# Drivers_Matrices.net
KiCad netlist of a schematic drawn in Altium Designer
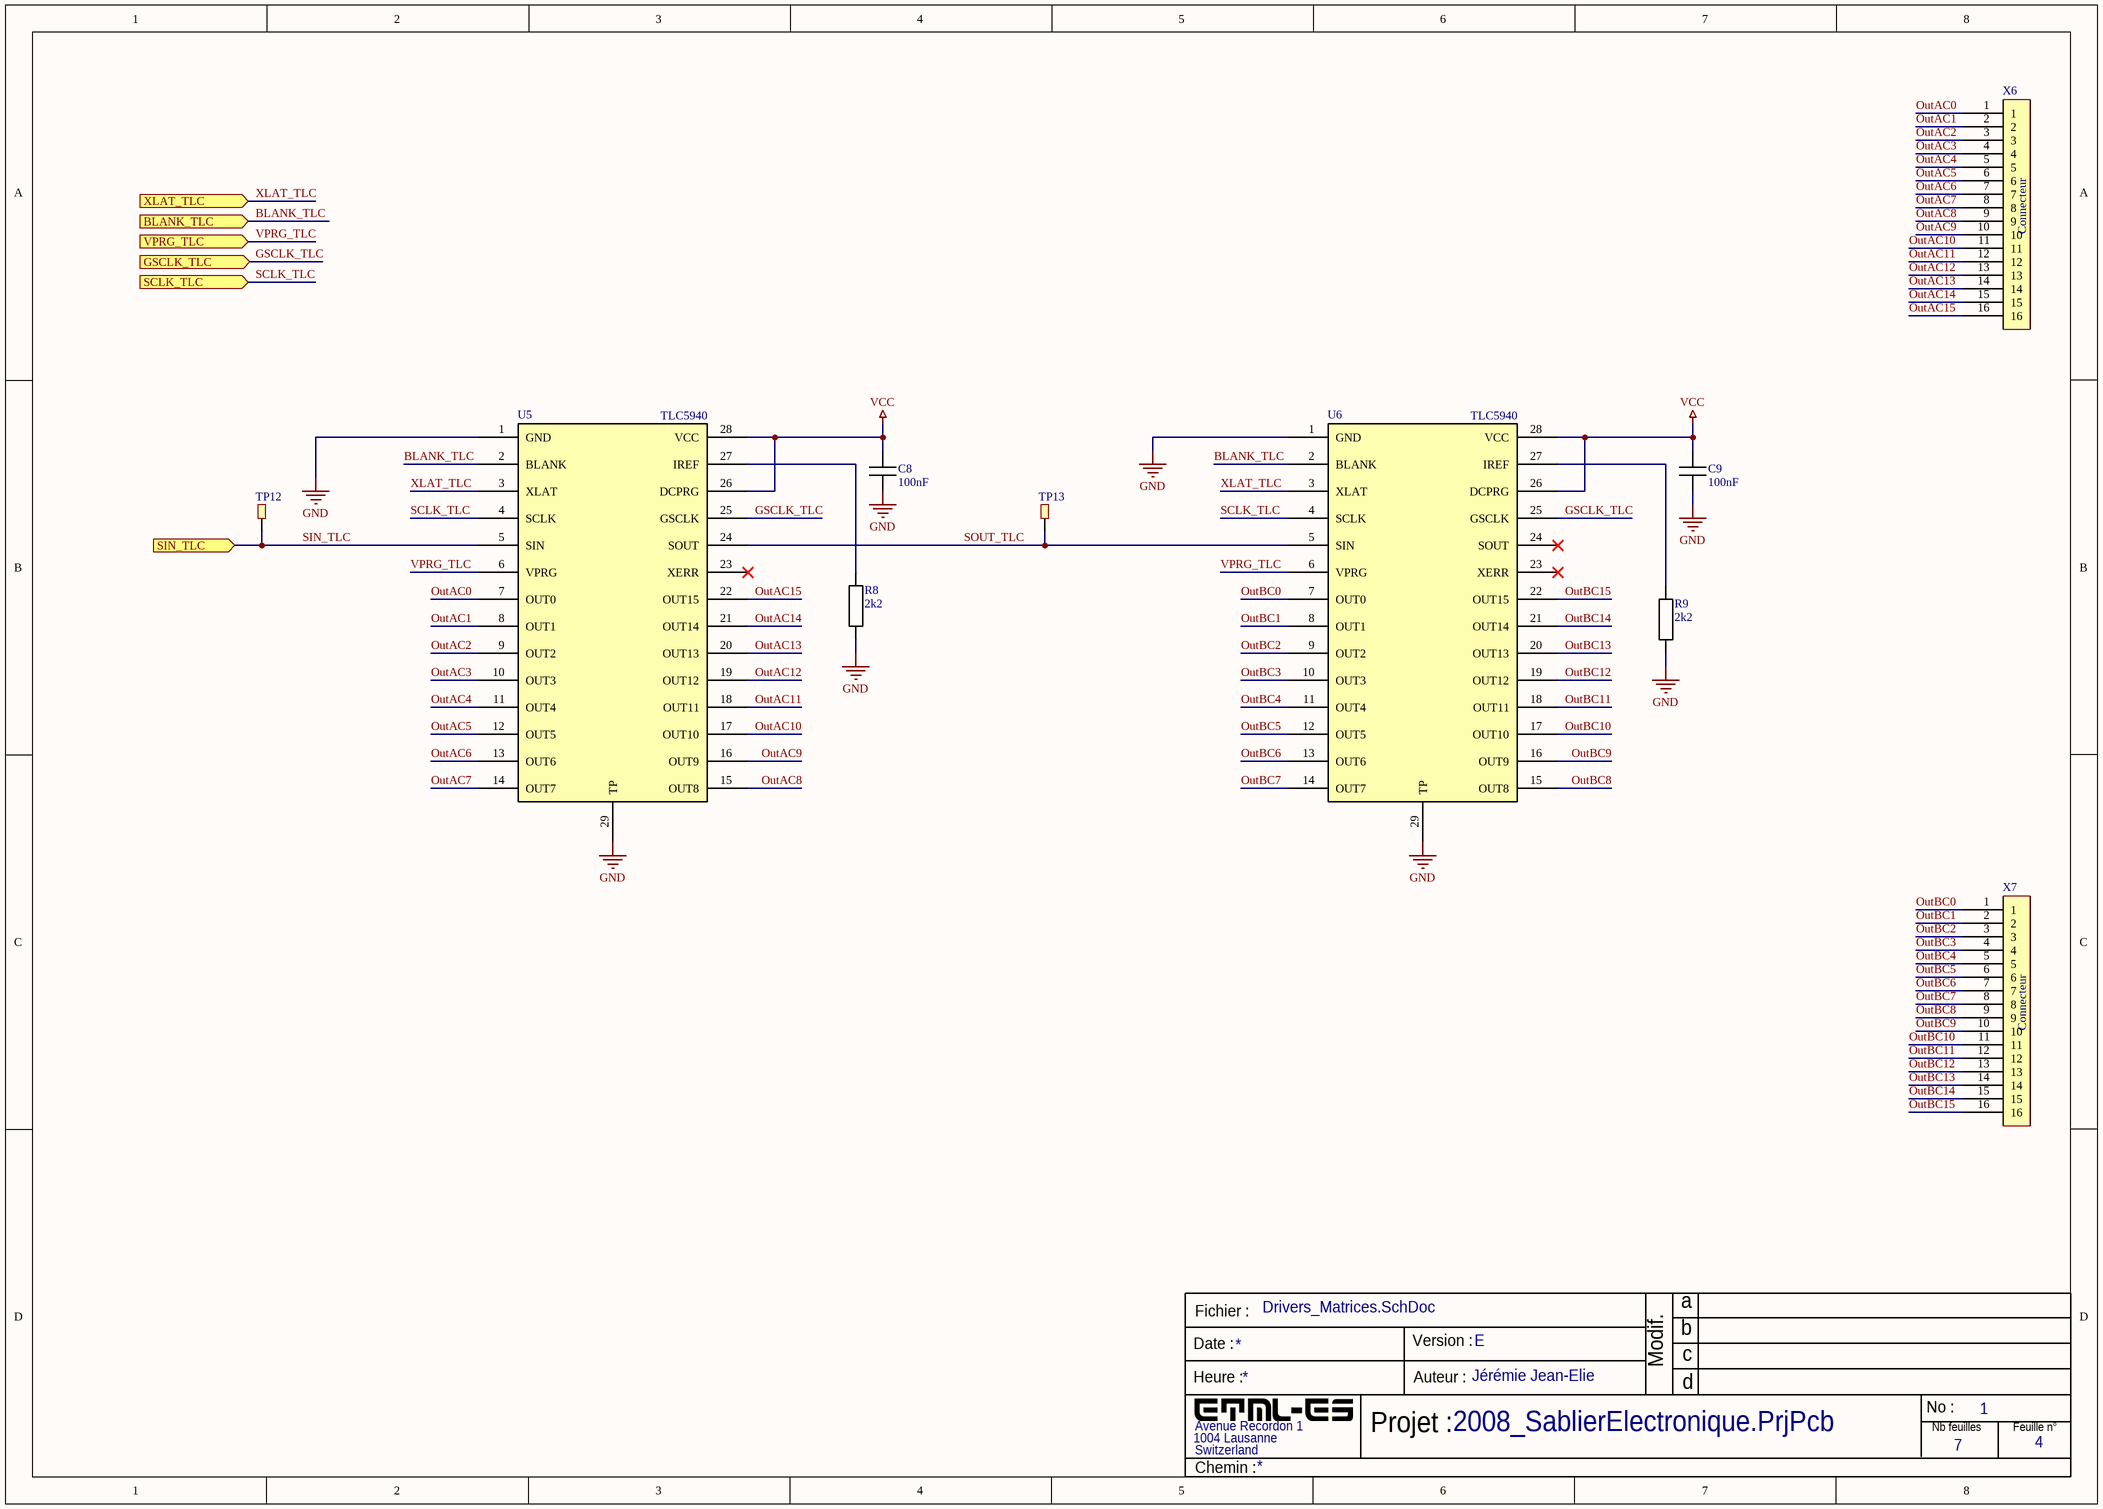
[diagram p0: Drivers_Matrices.SchDoc]

(export (version "E")
  (design (tool "Eeschema 10.0.6"))
  (components
    (comp (ref "C8")
      (value "100nF")
      (footprint "CAPC1608X08M")
      (description "CAPC 100nF X7R 50V 10% 1608 (0603 INCH)")
      (fields (field (name "VOLTAGE") "50V") (field (name "MANUFACTURER") "TDK"))
      (libsource (lib "ETML-ES") (part "CAP"))
    )
    (comp (ref "C9")
      (value "100nF")
      (footprint "CAPC1608X08M")
      (description "CAPC 100nF X7R 50V 10% 1608 (0603 INCH)")
      (fields (field (name "VOLTAGE") "50V") (field (name "MANUFACTURER") "TDK"))
      (libsource (lib "ETML-ES") (part "CAP"))
    )
    (comp (ref "R8")
      (value "2k2")
      (footprint "RESC1608X06M")
      (description "RES 2.2kohm  ±1% 0.1W  1608 (0603 INCH)")
      (fields (field (name "POWER") "0.1W") (field (name "VOLTAGE") "75V"))
      (libsource (lib "ETML-ES") (part "RES"))
    )
    (comp (ref "R9")
      (value "2k2")
      (footprint "RESC1608X06M")
      (description "RES 2.2kohm  ±1% 0.1W  1608 (0603 INCH)")
      (fields (field (name "POWER") "0.1W") (field (name "VOLTAGE") "75V"))
      (libsource (lib "ETML-ES") (part "RES"))
    )
    (comp (ref "TP12")
      (value "TestPoint")
      (footprint "KEYSTONE_5019")
      (libsource (lib "Schlib1") (part "TestPoint"))
    )
    (comp (ref "TP13")
      (value "TestPoint")
      (footprint "KEYSTONE_5019")
      (libsource (lib "Schlib1") (part "TestPoint"))
    )
    (comp (ref "U5")
      (value "TLC5940")
      (footprint "TSOP65P640X120_HS-29N")
      (libsource (lib "Schlib1") (part "TLC5940"))
    )
    (comp (ref "U6")
      (value "TLC5940")
      (footprint "TSOP65P640X120_HS-29N")
      (libsource (lib "Schlib1") (part "TLC5940"))
    )
    (comp (ref "X6")
      (value "~")
      (footprint "MOLEX_2x8")
      (libsource (lib "2008_SablierElectronique_SCHLIB") (part "Mâle DIN 8 x 8"))
    )
    (comp (ref "X7")
      (value "~")
      (footprint "MOLEX_2x8")
      (libsource (lib "2008_SablierElectronique_SCHLIB") (part "Mâle DIN 8 x 8"))
    )
  )
  (nets
    (net (code "1") (name "/BLANK_TLC") (class "Default")
      (node (ref "U5") (pin "2") (pinfunction "BLANK_2") (pintype "passive"))
      (node (ref "U6") (pin "2") (pinfunction "BLANK_2") (pintype "passive"))
    )
    (net (code "2") (name "/GSCLK_TLC") (class "Default")
      (node (ref "U5") (pin "25") (pinfunction "GSCLK_25") (pintype "passive"))
      (node (ref "U6") (pin "25") (pinfunction "GSCLK_25") (pintype "passive"))
    )
    (net (code "3") (name "/OutAC0") (class "Default")
      (node (ref "U5") (pin "7") (pinfunction "OUT0_7") (pintype "passive"))
      (node (ref "X6") (pin "1") (pinfunction "1_1") (pintype "passive"))
    )
    (net (code "4") (name "/OutAC1") (class "Default")
      (node (ref "U5") (pin "8") (pinfunction "OUT1_8") (pintype "passive"))
      (node (ref "X6") (pin "2") (pinfunction "2_2") (pintype "passive"))
    )
    (net (code "5") (name "/OutAC2") (class "Default")
      (node (ref "U5") (pin "9") (pinfunction "OUT2_9") (pintype "passive"))
      (node (ref "X6") (pin "3") (pinfunction "3_3") (pintype "passive"))
    )
    (net (code "6") (name "/OutAC3") (class "Default")
      (node (ref "U5") (pin "10") (pinfunction "OUT3_10") (pintype "passive"))
      (node (ref "X6") (pin "4") (pinfunction "4_4") (pintype "passive"))
    )
    (net (code "7") (name "/OutAC4") (class "Default")
      (node (ref "U5") (pin "11") (pinfunction "OUT4_11") (pintype "passive"))
      (node (ref "X6") (pin "5") (pinfunction "5_5") (pintype "passive"))
    )
    (net (code "8") (name "/OutAC5") (class "Default")
      (node (ref "U5") (pin "12") (pinfunction "OUT5_12") (pintype "passive"))
      (node (ref "X6") (pin "6") (pinfunction "6_6") (pintype "passive"))
    )
    (net (code "9") (name "/OutAC6") (class "Default")
      (node (ref "U5") (pin "13") (pinfunction "OUT6_13") (pintype "passive"))
      (node (ref "X6") (pin "7") (pinfunction "7_7") (pintype "passive"))
    )
    (net (code "10") (name "/OutAC7") (class "Default")
      (node (ref "U5") (pin "14") (pinfunction "OUT7_14") (pintype "passive"))
      (node (ref "X6") (pin "8") (pinfunction "8_8") (pintype "passive"))
    )
    (net (code "11") (name "/OutAC8") (class "Default")
      (node (ref "U5") (pin "15") (pinfunction "OUT8_15") (pintype "passive"))
      (node (ref "X6") (pin "9") (pinfunction "9_9") (pintype "passive"))
    )
    (net (code "12") (name "/OutAC9") (class "Default")
      (node (ref "U5") (pin "16") (pinfunction "OUT9_16") (pintype "passive"))
      (node (ref "X6") (pin "10") (pinfunction "10_10") (pintype "passive"))
    )
    (net (code "13") (name "/OutAC10") (class "Default")
      (node (ref "U5") (pin "17") (pinfunction "OUT10_17") (pintype "passive"))
      (node (ref "X6") (pin "11") (pinfunction "11_11") (pintype "passive"))
    )
    (net (code "14") (name "/OutAC11") (class "Default")
      (node (ref "U5") (pin "18") (pinfunction "OUT11_18") (pintype "passive"))
      (node (ref "X6") (pin "12") (pinfunction "12_12") (pintype "passive"))
    )
    (net (code "15") (name "/OutAC12") (class "Default")
      (node (ref "U5") (pin "19") (pinfunction "OUT12_19") (pintype "passive"))
      (node (ref "X6") (pin "13") (pinfunction "13_13") (pintype "passive"))
    )
    (net (code "16") (name "/OutAC13") (class "Default")
      (node (ref "U5") (pin "20") (pinfunction "OUT13_20") (pintype "passive"))
      (node (ref "X6") (pin "14") (pinfunction "14_14") (pintype "passive"))
    )
    (net (code "17") (name "/OutAC14") (class "Default")
      (node (ref "U5") (pin "21") (pinfunction "OUT14_21") (pintype "passive"))
      (node (ref "X6") (pin "15") (pinfunction "15_15") (pintype "passive"))
    )
    (net (code "18") (name "/OutAC15") (class "Default")
      (node (ref "U5") (pin "22") (pinfunction "OUT15_22") (pintype "passive"))
      (node (ref "X6") (pin "16") (pinfunction "16_16") (pintype "passive"))
    )
    (net (code "19") (name "/OutBC0") (class "Default")
      (node (ref "U6") (pin "7") (pinfunction "OUT0_7") (pintype "passive"))
      (node (ref "X7") (pin "1") (pinfunction "1_1") (pintype "passive"))
    )
    (net (code "20") (name "/OutBC1") (class "Default")
      (node (ref "U6") (pin "8") (pinfunction "OUT1_8") (pintype "passive"))
      (node (ref "X7") (pin "2") (pinfunction "2_2") (pintype "passive"))
    )
    (net (code "21") (name "/OutBC2") (class "Default")
      (node (ref "U6") (pin "9") (pinfunction "OUT2_9") (pintype "passive"))
      (node (ref "X7") (pin "3") (pinfunction "3_3") (pintype "passive"))
    )
    (net (code "22") (name "/OutBC3") (class "Default")
      (node (ref "U6") (pin "10") (pinfunction "OUT3_10") (pintype "passive"))
      (node (ref "X7") (pin "4") (pinfunction "4_4") (pintype "passive"))
    )
    (net (code "23") (name "/OutBC4") (class "Default")
      (node (ref "U6") (pin "11") (pinfunction "OUT4_11") (pintype "passive"))
      (node (ref "X7") (pin "5") (pinfunction "5_5") (pintype "passive"))
    )
    (net (code "24") (name "/OutBC5") (class "Default")
      (node (ref "U6") (pin "12") (pinfunction "OUT5_12") (pintype "passive"))
      (node (ref "X7") (pin "6") (pinfunction "6_6") (pintype "passive"))
    )
    (net (code "25") (name "/OutBC6") (class "Default")
      (node (ref "U6") (pin "13") (pinfunction "OUT6_13") (pintype "passive"))
      (node (ref "X7") (pin "7") (pinfunction "7_7") (pintype "passive"))
    )
    (net (code "26") (name "/OutBC7") (class "Default")
      (node (ref "U6") (pin "14") (pinfunction "OUT7_14") (pintype "passive"))
      (node (ref "X7") (pin "8") (pinfunction "8_8") (pintype "passive"))
    )
    (net (code "27") (name "/OutBC8") (class "Default")
      (node (ref "U6") (pin "15") (pinfunction "OUT8_15") (pintype "passive"))
      (node (ref "X7") (pin "9") (pinfunction "9_9") (pintype "passive"))
    )
    (net (code "28") (name "/OutBC9") (class "Default")
      (node (ref "U6") (pin "16") (pinfunction "OUT9_16") (pintype "passive"))
      (node (ref "X7") (pin "10") (pinfunction "10_10") (pintype "passive"))
    )
    (net (code "29") (name "/OutBC10") (class "Default")
      (node (ref "U6") (pin "17") (pinfunction "OUT10_17") (pintype "passive"))
      (node (ref "X7") (pin "11") (pinfunction "11_11") (pintype "passive"))
    )
    (net (code "30") (name "/OutBC11") (class "Default")
      (node (ref "U6") (pin "18") (pinfunction "OUT11_18") (pintype "passive"))
      (node (ref "X7") (pin "12") (pinfunction "12_12") (pintype "passive"))
    )
    (net (code "31") (name "/OutBC12") (class "Default")
      (node (ref "U6") (pin "19") (pinfunction "OUT12_19") (pintype "passive"))
      (node (ref "X7") (pin "13") (pinfunction "13_13") (pintype "passive"))
    )
    (net (code "32") (name "/OutBC13") (class "Default")
      (node (ref "U6") (pin "20") (pinfunction "OUT13_20") (pintype "passive"))
      (node (ref "X7") (pin "14") (pinfunction "14_14") (pintype "passive"))
    )
    (net (code "33") (name "/OutBC14") (class "Default")
      (node (ref "U6") (pin "21") (pinfunction "OUT14_21") (pintype "passive"))
      (node (ref "X7") (pin "15") (pinfunction "15_15") (pintype "passive"))
    )
    (net (code "34") (name "/OutBC15") (class "Default")
      (node (ref "U6") (pin "22") (pinfunction "OUT15_22") (pintype "passive"))
      (node (ref "X7") (pin "16") (pinfunction "16_16") (pintype "passive"))
    )
    (net (code "35") (name "/SCLK_TLC") (class "Default")
      (node (ref "U5") (pin "4") (pinfunction "SCLK_4") (pintype "passive"))
      (node (ref "U6") (pin "4") (pinfunction "SCLK_4") (pintype "passive"))
    )
    (net (code "36") (name "/SIN_TLC") (class "Default")
      (node (ref "TP12") (pin "1") (pinfunction "1_1") (pintype "passive"))
      (node (ref "U5") (pin "5") (pinfunction "SIN_5") (pintype "passive"))
    )
    (net (code "37") (name "/SOUT_TLC") (class "Default")
      (node (ref "TP13") (pin "1") (pinfunction "1_1") (pintype "passive"))
      (node (ref "U5") (pin "24") (pinfunction "SOUT_24") (pintype "passive"))
      (node (ref "U6") (pin "5") (pinfunction "SIN_5") (pintype "passive"))
    )
    (net (code "38") (name "/VPRG_TLC") (class "Default")
      (node (ref "U5") (pin "6") (pinfunction "VPRG_6") (pintype "passive"))
      (node (ref "U6") (pin "6") (pinfunction "VPRG_6") (pintype "passive"))
    )
    (net (code "39") (name "/XLAT_TLC") (class "Default")
      (node (ref "U5") (pin "3") (pinfunction "XLAT_3") (pintype "passive"))
      (node (ref "U6") (pin "3") (pinfunction "XLAT_3") (pintype "passive"))
    )
    (net (code "40") (name "GND") (class "Default")
      (node (ref "C8") (pin "1") (pinfunction "1_1") (pintype "passive"))
      (node (ref "C9") (pin "1") (pinfunction "1_1") (pintype "passive"))
      (node (ref "R8") (pin "1") (pinfunction "1_1") (pintype "passive"))
      (node (ref "R9") (pin "1") (pinfunction "1_1") (pintype "passive"))
      (node (ref "U5") (pin "1") (pinfunction "GND_1") (pintype "passive"))
      (node (ref "U5") (pin "29") (pinfunction "TP_29") (pintype "passive"))
      (node (ref "U6") (pin "1") (pinfunction "GND_1") (pintype "passive"))
      (node (ref "U6") (pin "29") (pinfunction "TP_29") (pintype "passive"))
    )
    (net (code "41") (name "Net-(U5-IREF)") (class "Default")
      (node (ref "R8") (pin "2") (pinfunction "2_2") (pintype "passive"))
      (node (ref "U5") (pin "27") (pinfunction "IREF_27") (pintype "passive"))
    )
    (net (code "42") (name "Net-(U6-IREF)") (class "Default")
      (node (ref "R9") (pin "2") (pinfunction "2_2") (pintype "passive"))
      (node (ref "U6") (pin "27") (pinfunction "IREF_27") (pintype "passive"))
    )
    (net (code "43") (name "VCC") (class "Default")
      (node (ref "C8") (pin "2") (pinfunction "2_2") (pintype "passive"))
      (node (ref "C9") (pin "2") (pinfunction "2_2") (pintype "passive"))
      (node (ref "U5") (pin "26") (pinfunction "DCPRG_26") (pintype "passive"))
      (node (ref "U5") (pin "28") (pinfunction "VCC_28") (pintype "passive"))
      (node (ref "U6") (pin "26") (pinfunction "DCPRG_26") (pintype "passive"))
      (node (ref "U6") (pin "28") (pinfunction "VCC_28") (pintype "passive"))
    )
    (net (code "44") (name "unconnected-(U5-XERR-Pad23)") (class "Default")
      (node (ref "U5") (pin "23") (pinfunction "XERR_23") (pintype "passive+no_connect"))
    )
    (net (code "45") (name "unconnected-(U6-SOUT-Pad24)") (class "Default")
      (node (ref "U6") (pin "24") (pinfunction "SOUT_24") (pintype "passive+no_connect"))
    )
    (net (code "46") (name "unconnected-(U6-XERR-Pad23)") (class "Default")
      (node (ref "U6") (pin "23") (pinfunction "XERR_23") (pintype "passive+no_connect"))
    )
  )
)
